# Potencia.net
KiCad netlist of a schematic drawn in Altium Designer
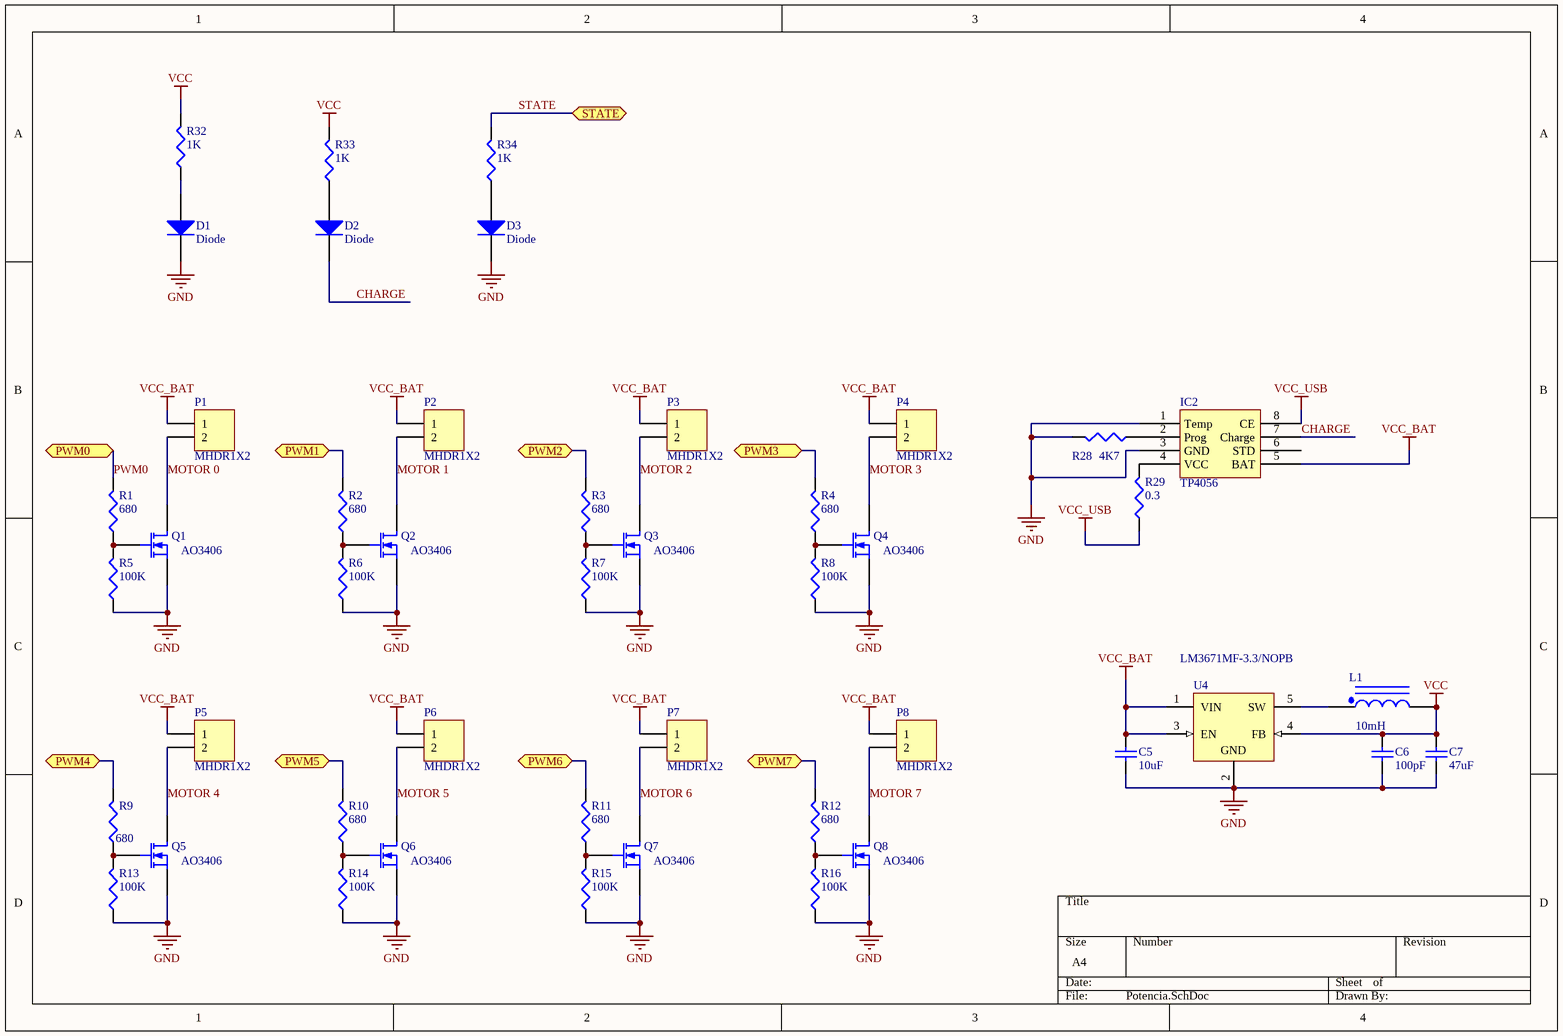
[diagram p0: Potencia.SchDoc]

(export (version "E")
  (design (tool "Eeschema 10.0.6"))
  (components
    (comp (ref "C5")
      (value "10uF")
      (footprint "Miscellaneous Devices:6-0805_L")
      (description "Capacitor")
      (fields (field (name "Comment") "Cap") (field (name "PUBLISHER") "Altium Limited"))
      (libsource (lib "Miscellaneous Devices") (part "Cap"))
    )
    (comp (ref "C6")
      (value "100pF")
      (footprint "Miscellaneous Devices:6-0805_L")
      (description "Capacitor")
      (fields (field (name "Comment") "Cap") (field (name "PUBLISHER") "Altium Limited"))
      (libsource (lib "Miscellaneous Devices") (part "Cap"))
    )
    (comp (ref "C7")
      (value "47uF")
      (footprint "Miscellaneous Devices:6-0805_L")
      (description "Capacitor")
      (fields (field (name "Comment") "Cap") (field (name "PUBLISHER") "Altium Limited"))
      (libsource (lib "Miscellaneous Devices") (part "Cap"))
    )
    (comp (ref "D1")
      (value "Diode")
      (footprint "PBL - SMD Packages:LED-0805")
      (description "Default Diode")
      (fields (field (name "PUBLISHER") "Altium Limited"))
      (libsource (lib "Miscellaneous Devices") (part "Diode"))
    )
    (comp (ref "D2")
      (value "Diode")
      (footprint "PBL - SMD Packages:LED-0805")
      (description "Default Diode")
      (fields (field (name "PUBLISHER") "Altium Limited"))
      (libsource (lib "Miscellaneous Devices") (part "Diode"))
    )
    (comp (ref "D3")
      (value "Diode")
      (footprint "PBL - SMD Packages:LED-0805")
      (description "Default Diode")
      (fields (field (name "PUBLISHER") "Altium Limited"))
      (libsource (lib "Miscellaneous Devices") (part "Diode"))
    )
    (comp (ref "IC2")
      (value "TP4056")
      (footprint "SOIC127P600X175-8AN")
      (libsource (lib "Libreria General") (part "TP4056"))
    )
    (comp (ref "L1")
      (value "10mH")
      (footprint "Inductor CD43")
      (description "Magnetic-Core Inductor with Winding Polarity Marking")
      (fields (field (name "Comment") "Inductor Iron Dot") (field (name "PUBLISHER") "Altium Limited"))
      (libsource (lib "Miscellaneous Devices") (part "Inductor Iron Dot"))
    )
    (comp (ref "P1")
      (value "MHDR1X2")
      (footprint "MHDR1X2")
      (description "Header, 2-Pin")
      (fields (field (name "PUBLISHER") "Altium Limited"))
      (libsource (lib "Miscellaneous Connectors") (part "MHDR1X2"))
    )
    (comp (ref "P2")
      (value "MHDR1X2")
      (footprint "MHDR1X2")
      (description "Header, 2-Pin")
      (fields (field (name "PUBLISHER") "Altium Limited"))
      (libsource (lib "Miscellaneous Connectors") (part "MHDR1X2"))
    )
    (comp (ref "P3")
      (value "MHDR1X2")
      (footprint "MHDR1X2")
      (description "Header, 2-Pin")
      (fields (field (name "PUBLISHER") "Altium Limited"))
      (libsource (lib "Miscellaneous Connectors") (part "MHDR1X2"))
    )
    (comp (ref "P4")
      (value "MHDR1X2")
      (footprint "MHDR1X2")
      (description "Header, 2-Pin")
      (fields (field (name "PUBLISHER") "Altium Limited"))
      (libsource (lib "Miscellaneous Connectors") (part "MHDR1X2"))
    )
    (comp (ref "P5")
      (value "MHDR1X2")
      (footprint "MHDR1X2")
      (description "Header, 2-Pin")
      (fields (field (name "PUBLISHER") "Altium Limited"))
      (libsource (lib "Miscellaneous Connectors") (part "MHDR1X2"))
    )
    (comp (ref "P6")
      (value "MHDR1X2")
      (footprint "MHDR1X2")
      (description "Header, 2-Pin")
      (fields (field (name "PUBLISHER") "Altium Limited"))
      (libsource (lib "Miscellaneous Connectors") (part "MHDR1X2"))
    )
    (comp (ref "P7")
      (value "MHDR1X2")
      (footprint "MHDR1X2")
      (description "Header, 2-Pin")
      (fields (field (name "PUBLISHER") "Altium Limited"))
      (libsource (lib "Miscellaneous Connectors") (part "MHDR1X2"))
    )
    (comp (ref "P8")
      (value "MHDR1X2")
      (footprint "MHDR1X2")
      (description "Header, 2-Pin")
      (fields (field (name "PUBLISHER") "Altium Limited"))
      (libsource (lib "Miscellaneous Connectors") (part "MHDR1X2"))
    )
    (comp (ref "Q1")
      (value "AO3406")
      (footprint "PBL - SMD Packages:SOT23-3")
      (description "N-Channel MOSFET")
      (fields (field (name "PUBLISHER") "Altium Limited"))
      (libsource (lib "Miscellaneous Devices") (part "MOSFET-N"))
    )
    (comp (ref "Q2")
      (value "AO3406")
      (footprint "PBL - SMD Packages:SOT23-3")
      (description "N-Channel MOSFET")
      (fields (field (name "PUBLISHER") "Altium Limited"))
      (libsource (lib "Miscellaneous Devices") (part "MOSFET-N"))
    )
    (comp (ref "Q3")
      (value "AO3406")
      (footprint "PBL - SMD Packages:SOT23-3")
      (description "N-Channel MOSFET")
      (fields (field (name "PUBLISHER") "Altium Limited"))
      (libsource (lib "Miscellaneous Devices") (part "MOSFET-N"))
    )
    (comp (ref "Q4")
      (value "AO3406")
      (footprint "PBL - SMD Packages:SOT23-3")
      (description "N-Channel MOSFET")
      (fields (field (name "PUBLISHER") "Altium Limited"))
      (libsource (lib "Miscellaneous Devices") (part "MOSFET-N"))
    )
    (comp (ref "Q5")
      (value "AO3406")
      (footprint "PBL - SMD Packages:SOT23-3")
      (description "N-Channel MOSFET")
      (fields (field (name "PUBLISHER") "Altium Limited"))
      (libsource (lib "Miscellaneous Devices") (part "MOSFET-N"))
    )
    (comp (ref "Q6")
      (value "AO3406")
      (footprint "PBL - SMD Packages:SOT23-3")
      (description "N-Channel MOSFET")
      (fields (field (name "PUBLISHER") "Altium Limited"))
      (libsource (lib "Miscellaneous Devices") (part "MOSFET-N"))
    )
    (comp (ref "Q7")
      (value "AO3406")
      (footprint "PBL - SMD Packages:SOT23-3")
      (description "N-Channel MOSFET")
      (fields (field (name "PUBLISHER") "Altium Limited"))
      (libsource (lib "Miscellaneous Devices") (part "MOSFET-N"))
    )
    (comp (ref "Q8")
      (value "AO3406")
      (footprint "PBL - SMD Packages:SOT23-3")
      (description "N-Channel MOSFET")
      (fields (field (name "PUBLISHER") "Altium Limited"))
      (libsource (lib "Miscellaneous Devices") (part "MOSFET-N"))
    )
    (comp (ref "R1")
      (value "680")
      (footprint "6-0805_N")
      (description "Resistor")
      (fields (field (name "Comment") "Res3") (field (name "PUBLISHER") "Altium Limited"))
      (libsource (lib "Miscellaneous Devices") (part "Res3"))
    )
    (comp (ref "R2")
      (value "680")
      (footprint "6-0805_N")
      (description "Resistor")
      (fields (field (name "Comment") "Res3") (field (name "PUBLISHER") "Altium Limited"))
      (libsource (lib "Miscellaneous Devices") (part "Res3"))
    )
    (comp (ref "R3")
      (value "680")
      (footprint "6-0805_N")
      (description "Resistor")
      (fields (field (name "Comment") "Res3") (field (name "PUBLISHER") "Altium Limited"))
      (libsource (lib "Miscellaneous Devices") (part "Res3"))
    )
    (comp (ref "R4")
      (value "680")
      (footprint "6-0805_N")
      (description "Resistor")
      (fields (field (name "Comment") "Res3") (field (name "PUBLISHER") "Altium Limited"))
      (libsource (lib "Miscellaneous Devices") (part "Res3"))
    )
    (comp (ref "R5")
      (value "100K")
      (footprint "6-0805_N")
      (description "Resistor")
      (fields (field (name "Comment") "Res3") (field (name "PUBLISHER") "Altium Limited"))
      (libsource (lib "Miscellaneous Devices") (part "Res3"))
    )
    (comp (ref "R6")
      (value "100K")
      (footprint "6-0805_N")
      (description "Resistor")
      (fields (field (name "Comment") "Res3") (field (name "PUBLISHER") "Altium Limited"))
      (libsource (lib "Miscellaneous Devices") (part "Res3"))
    )
    (comp (ref "R7")
      (value "100K")
      (footprint "6-0805_N")
      (description "Resistor")
      (fields (field (name "Comment") "Res3") (field (name "PUBLISHER") "Altium Limited"))
      (libsource (lib "Miscellaneous Devices") (part "Res3"))
    )
    (comp (ref "R8")
      (value "100K")
      (footprint "6-0805_N")
      (description "Resistor")
      (fields (field (name "Comment") "Res3") (field (name "PUBLISHER") "Altium Limited"))
      (libsource (lib "Miscellaneous Devices") (part "Res3"))
    )
    (comp (ref "R9")
      (value "680")
      (footprint "6-0805_N")
      (description "Resistor")
      (fields (field (name "Comment") "Res3") (field (name "PUBLISHER") "Altium Limited"))
      (libsource (lib "Miscellaneous Devices") (part "Res3"))
    )
    (comp (ref "R10")
      (value "680")
      (footprint "6-0805_N")
      (description "Resistor")
      (fields (field (name "Comment") "Res3") (field (name "PUBLISHER") "Altium Limited"))
      (libsource (lib "Miscellaneous Devices") (part "Res3"))
    )
    (comp (ref "R11")
      (value "680")
      (footprint "6-0805_N")
      (description "Resistor")
      (fields (field (name "Comment") "Res3") (field (name "PUBLISHER") "Altium Limited"))
      (libsource (lib "Miscellaneous Devices") (part "Res3"))
    )
    (comp (ref "R12")
      (value "680")
      (footprint "6-0805_N")
      (description "Resistor")
      (fields (field (name "Comment") "Res3") (field (name "PUBLISHER") "Altium Limited"))
      (libsource (lib "Miscellaneous Devices") (part "Res3"))
    )
    (comp (ref "R13")
      (value "100K")
      (footprint "6-0805_N")
      (description "Resistor")
      (fields (field (name "Comment") "Res3") (field (name "PUBLISHER") "Altium Limited"))
      (libsource (lib "Miscellaneous Devices") (part "Res3"))
    )
    (comp (ref "R14")
      (value "100K")
      (footprint "6-0805_N")
      (description "Resistor")
      (fields (field (name "Comment") "Res3") (field (name "PUBLISHER") "Altium Limited"))
      (libsource (lib "Miscellaneous Devices") (part "Res3"))
    )
    (comp (ref "R15")
      (value "100K")
      (footprint "6-0805_N")
      (description "Resistor")
      (fields (field (name "Comment") "Res3") (field (name "PUBLISHER") "Altium Limited"))
      (libsource (lib "Miscellaneous Devices") (part "Res3"))
    )
    (comp (ref "R16")
      (value "100K")
      (footprint "6-0805_N")
      (description "Resistor")
      (fields (field (name "Comment") "Res3") (field (name "PUBLISHER") "Altium Limited"))
      (libsource (lib "Miscellaneous Devices") (part "Res3"))
    )
    (comp (ref "R28")
      (value "4K7")
      (footprint "6-0805_N")
      (description "Resistor")
      (fields (field (name "Comment") "Res3") (field (name "PUBLISHER") "Altium Limited"))
      (libsource (lib "Miscellaneous Devices") (part "Res3"))
    )
    (comp (ref "R29")
      (value "0.3")
      (footprint "C1206")
      (description "Resistor")
      (fields (field (name "Comment") "Res3") (field (name "PUBLISHER") "Altium Limited"))
      (libsource (lib "Miscellaneous Devices") (part "Res3"))
    )
    (comp (ref "R32")
      (value "1K")
      (footprint "6-0805_N")
      (description "Resistor")
      (fields (field (name "Comment") "Res3") (field (name "PUBLISHER") "Altium Limited"))
      (libsource (lib "Miscellaneous Devices") (part "Res3"))
    )
    (comp (ref "R33")
      (value "1K")
      (footprint "6-0805_N")
      (description "Resistor")
      (fields (field (name "Comment") "Res3") (field (name "PUBLISHER") "Altium Limited"))
      (libsource (lib "Miscellaneous Devices") (part "Res3"))
    )
    (comp (ref "R34")
      (value "1K")
      (footprint "6-0805_N")
      (description "Resistor")
      (fields (field (name "Comment") "Res3") (field (name "PUBLISHER") "Altium Limited"))
      (libsource (lib "Miscellaneous Devices") (part "Res3"))
    )
    (comp (ref "U4")
      (value "LM3671MF-3.3/NOPB")
      (footprint "MF05A_N")
      (description "2MHz, 600mA Step-Down DC-DC Converter, 5-pin SOT-23, Pb-Free")
      (fields
        (field (name "MANUFACTURER") "National Semiconductor")
        (field (name "PUBLISHER") "Altium Limited")
      )
      (libsource (lib "NSC MiscPower") (part "LM3671MF-3.3/NOPB"))
    )
  )
  (nets
    (net (code "1") (name "/CHARGE") (class "Default")
      (node (ref "D2") (pin "2") (pinfunction "K_2") (pintype "passive"))
      (node (ref "IC2") (pin "7") (pinfunction "Charge_7") (pintype "passive"))
    )
    (net (code "2") (name "/MOTOR 0") (class "Default")
      (node (ref "P1") (pin "2") (pinfunction "2_2") (pintype "passive"))
      (node (ref "Q1") (pin "1") (pinfunction "D_1") (pintype "passive"))
    )
    (net (code "3") (name "/MOTOR 1") (class "Default")
      (node (ref "P2") (pin "2") (pinfunction "2_2") (pintype "passive"))
      (node (ref "Q2") (pin "1") (pinfunction "D_1") (pintype "passive"))
    )
    (net (code "4") (name "/MOTOR 2") (class "Default")
      (node (ref "P3") (pin "2") (pinfunction "2_2") (pintype "passive"))
      (node (ref "Q3") (pin "1") (pinfunction "D_1") (pintype "passive"))
    )
    (net (code "5") (name "/MOTOR 3") (class "Default")
      (node (ref "P4") (pin "2") (pinfunction "2_2") (pintype "passive"))
      (node (ref "Q4") (pin "1") (pinfunction "D_1") (pintype "passive"))
    )
    (net (code "6") (name "/MOTOR 4") (class "Default")
      (node (ref "P5") (pin "2") (pinfunction "2_2") (pintype "passive"))
      (node (ref "Q5") (pin "1") (pinfunction "D_1") (pintype "passive"))
    )
    (net (code "7") (name "/MOTOR 5") (class "Default")
      (node (ref "P6") (pin "2") (pinfunction "2_2") (pintype "passive"))
      (node (ref "Q6") (pin "1") (pinfunction "D_1") (pintype "passive"))
    )
    (net (code "8") (name "/MOTOR 6") (class "Default")
      (node (ref "P7") (pin "2") (pinfunction "2_2") (pintype "passive"))
      (node (ref "Q7") (pin "1") (pinfunction "D_1") (pintype "passive"))
    )
    (net (code "9") (name "/MOTOR 7") (class "Default")
      (node (ref "P8") (pin "2") (pinfunction "2_2") (pintype "passive"))
      (node (ref "Q8") (pin "1") (pinfunction "D_1") (pintype "passive"))
    )
    (net (code "10") (name "/PWM0") (class "Default")
      (node (ref "R1") (pin "2") (pinfunction "2_2") (pintype "passive"))
    )
    (net (code "11") (name "/PWM1") (class "Default")
      (node (ref "R2") (pin "2") (pinfunction "2_2") (pintype "passive"))
    )
    (net (code "12") (name "/PWM2") (class "Default")
      (node (ref "R3") (pin "2") (pinfunction "2_2") (pintype "passive"))
    )
    (net (code "13") (name "/PWM3") (class "Default")
      (node (ref "R4") (pin "2") (pinfunction "2_2") (pintype "passive"))
    )
    (net (code "14") (name "/PWM4") (class "Default")
      (node (ref "R9") (pin "2") (pinfunction "2_2") (pintype "passive"))
    )
    (net (code "15") (name "/PWM5") (class "Default")
      (node (ref "R10") (pin "2") (pinfunction "2_2") (pintype "passive"))
    )
    (net (code "16") (name "/PWM6") (class "Default")
      (node (ref "R11") (pin "2") (pinfunction "2_2") (pintype "passive"))
    )
    (net (code "17") (name "/PWM7") (class "Default")
      (node (ref "R12") (pin "2") (pinfunction "2_2") (pintype "passive"))
    )
    (net (code "18") (name "/STATE") (class "Default")
      (node (ref "R34") (pin "2") (pinfunction "2_2") (pintype "passive"))
    )
    (net (code "19") (name "GND") (class "Default")
      (node (ref "C5") (pin "1") (pinfunction "1_1") (pintype "passive"))
      (node (ref "C6") (pin "1") (pinfunction "1_1") (pintype "passive"))
      (node (ref "C7") (pin "1") (pinfunction "1_1") (pintype "passive"))
      (node (ref "D1") (pin "2") (pinfunction "K_2") (pintype "passive"))
      (node (ref "D3") (pin "2") (pinfunction "K_2") (pintype "passive"))
      (node (ref "IC2") (pin "1") (pinfunction "Temp_1") (pintype "passive"))
      (node (ref "IC2") (pin "3") (pinfunction "GND_3") (pintype "passive"))
      (node (ref "Q1") (pin "3") (pinfunction "S_3") (pintype "passive"))
      (node (ref "Q2") (pin "3") (pinfunction "S_3") (pintype "passive"))
      (node (ref "Q3") (pin "3") (pinfunction "S_3") (pintype "passive"))
      (node (ref "Q4") (pin "3") (pinfunction "S_3") (pintype "passive"))
      (node (ref "Q5") (pin "3") (pinfunction "S_3") (pintype "passive"))
      (node (ref "Q6") (pin "3") (pinfunction "S_3") (pintype "passive"))
      (node (ref "Q7") (pin "3") (pinfunction "S_3") (pintype "passive"))
      (node (ref "Q8") (pin "3") (pinfunction "S_3") (pintype "passive"))
      (node (ref "R13") (pin "1") (pinfunction "1_1") (pintype "passive"))
      (node (ref "R14") (pin "1") (pinfunction "1_1") (pintype "passive"))
      (node (ref "R15") (pin "1") (pinfunction "1_1") (pintype "passive"))
      (node (ref "R16") (pin "1") (pinfunction "1_1") (pintype "passive"))
      (node (ref "R28") (pin "2") (pinfunction "2_2") (pintype "passive"))
      (node (ref "R5") (pin "1") (pinfunction "1_1") (pintype "passive"))
      (node (ref "R6") (pin "1") (pinfunction "1_1") (pintype "passive"))
      (node (ref "R7") (pin "1") (pinfunction "1_1") (pintype "passive"))
      (node (ref "R8") (pin "1") (pinfunction "1_1") (pintype "passive"))
      (node (ref "U4") (pin "2") (pinfunction "GND_2") (pintype "power_in"))
    )
    (net (code "20") (name "Net-(D1-A)") (class "Default")
      (node (ref "D1") (pin "1") (pinfunction "A_1") (pintype "passive"))
      (node (ref "R32") (pin "1") (pinfunction "1_1") (pintype "passive"))
    )
    (net (code "21") (name "Net-(D2-A)") (class "Default")
      (node (ref "D2") (pin "1") (pinfunction "A_1") (pintype "passive"))
      (node (ref "R33") (pin "1") (pinfunction "1_1") (pintype "passive"))
    )
    (net (code "22") (name "Net-(D3-A)") (class "Default")
      (node (ref "D3") (pin "1") (pinfunction "A_1") (pintype "passive"))
      (node (ref "R34") (pin "1") (pinfunction "1_1") (pintype "passive"))
    )
    (net (code "23") (name "Net-(IC2-Prog)") (class "Default")
      (node (ref "IC2") (pin "2") (pinfunction "Prog_2") (pintype "passive"))
      (node (ref "R28") (pin "1") (pinfunction "1_1") (pintype "passive"))
    )
    (net (code "24") (name "Net-(IC2-VCC)") (class "Default")
      (node (ref "IC2") (pin "4") (pinfunction "VCC_4") (pintype "passive"))
      (node (ref "R29") (pin "2") (pinfunction "2_2") (pintype "passive"))
    )
    (net (code "25") (name "Net-(Q1-G)") (class "Default")
      (node (ref "Q1") (pin "2") (pinfunction "G_2") (pintype "passive"))
      (node (ref "R1") (pin "1") (pinfunction "1_1") (pintype "passive"))
      (node (ref "R5") (pin "2") (pinfunction "2_2") (pintype "passive"))
    )
    (net (code "26") (name "Net-(Q2-G)") (class "Default")
      (node (ref "Q2") (pin "2") (pinfunction "G_2") (pintype "passive"))
      (node (ref "R2") (pin "1") (pinfunction "1_1") (pintype "passive"))
      (node (ref "R6") (pin "2") (pinfunction "2_2") (pintype "passive"))
    )
    (net (code "27") (name "Net-(Q3-G)") (class "Default")
      (node (ref "Q3") (pin "2") (pinfunction "G_2") (pintype "passive"))
      (node (ref "R3") (pin "1") (pinfunction "1_1") (pintype "passive"))
      (node (ref "R7") (pin "2") (pinfunction "2_2") (pintype "passive"))
    )
    (net (code "28") (name "Net-(Q4-G)") (class "Default")
      (node (ref "Q4") (pin "2") (pinfunction "G_2") (pintype "passive"))
      (node (ref "R4") (pin "1") (pinfunction "1_1") (pintype "passive"))
      (node (ref "R8") (pin "2") (pinfunction "2_2") (pintype "passive"))
    )
    (net (code "29") (name "Net-(Q5-G)") (class "Default")
      (node (ref "Q5") (pin "2") (pinfunction "G_2") (pintype "passive"))
      (node (ref "R13") (pin "2") (pinfunction "2_2") (pintype "passive"))
      (node (ref "R9") (pin "1") (pinfunction "1_1") (pintype "passive"))
    )
    (net (code "30") (name "Net-(Q6-G)") (class "Default")
      (node (ref "Q6") (pin "2") (pinfunction "G_2") (pintype "passive"))
      (node (ref "R10") (pin "1") (pinfunction "1_1") (pintype "passive"))
      (node (ref "R14") (pin "2") (pinfunction "2_2") (pintype "passive"))
    )
    (net (code "31") (name "Net-(Q7-G)") (class "Default")
      (node (ref "Q7") (pin "2") (pinfunction "G_2") (pintype "passive"))
      (node (ref "R11") (pin "1") (pinfunction "1_1") (pintype "passive"))
      (node (ref "R15") (pin "2") (pinfunction "2_2") (pintype "passive"))
    )
    (net (code "32") (name "Net-(Q8-G)") (class "Default")
      (node (ref "Q8") (pin "2") (pinfunction "G_2") (pintype "passive"))
      (node (ref "R12") (pin "1") (pinfunction "1_1") (pintype "passive"))
      (node (ref "R16") (pin "2") (pinfunction "2_2") (pintype "passive"))
    )
    (net (code "33") (name "Net-(U4-SW)") (class "Default")
      (node (ref "L1") (pin "1") (pinfunction "1_1") (pintype "passive"))
      (node (ref "U4") (pin "5") (pinfunction "SW_5") (pintype "power_in"))
    )
    (net (code "34") (name "VCC") (class "Default")
      (node (ref "C6") (pin "2") (pinfunction "2_2") (pintype "passive"))
      (node (ref "C7") (pin "2") (pinfunction "2_2") (pintype "passive"))
      (node (ref "L1") (pin "2") (pinfunction "2_2") (pintype "passive"))
      (node (ref "R32") (pin "2") (pinfunction "2_2") (pintype "passive"))
      (node (ref "R33") (pin "2") (pinfunction "2_2") (pintype "passive"))
      (node (ref "U4") (pin "4") (pinfunction "FB_4") (pintype "input"))
    )
    (net (code "35") (name "VCC_BAT") (class "Default")
      (node (ref "C5") (pin "2") (pinfunction "2_2") (pintype "passive"))
      (node (ref "IC2") (pin "5") (pinfunction "BAT_5") (pintype "passive"))
      (node (ref "P1") (pin "1") (pinfunction "1_1") (pintype "passive"))
      (node (ref "P2") (pin "1") (pinfunction "1_1") (pintype "passive"))
      (node (ref "P3") (pin "1") (pinfunction "1_1") (pintype "passive"))
      (node (ref "P4") (pin "1") (pinfunction "1_1") (pintype "passive"))
      (node (ref "P5") (pin "1") (pinfunction "1_1") (pintype "passive"))
      (node (ref "P6") (pin "1") (pinfunction "1_1") (pintype "passive"))
      (node (ref "P7") (pin "1") (pinfunction "1_1") (pintype "passive"))
      (node (ref "P8") (pin "1") (pinfunction "1_1") (pintype "passive"))
      (node (ref "U4") (pin "1") (pinfunction "VIN_1") (pintype "power_in"))
      (node (ref "U4") (pin "3") (pinfunction "EN_3") (pintype "input"))
    )
    (net (code "36") (name "VCC_USB") (class "Default")
      (node (ref "IC2") (pin "8") (pinfunction "CE_8") (pintype "passive"))
      (node (ref "R29") (pin "1") (pinfunction "1_1") (pintype "passive"))
    )
    (net (code "37") (name "unconnected-(IC2-STD-Pad6)") (class "Default")
      (node (ref "IC2") (pin "6") (pinfunction "STD_6") (pintype "passive"))
    )
  )
)
